# drv8833.net
KiCad netlist of a schematic drawn in EAGLE
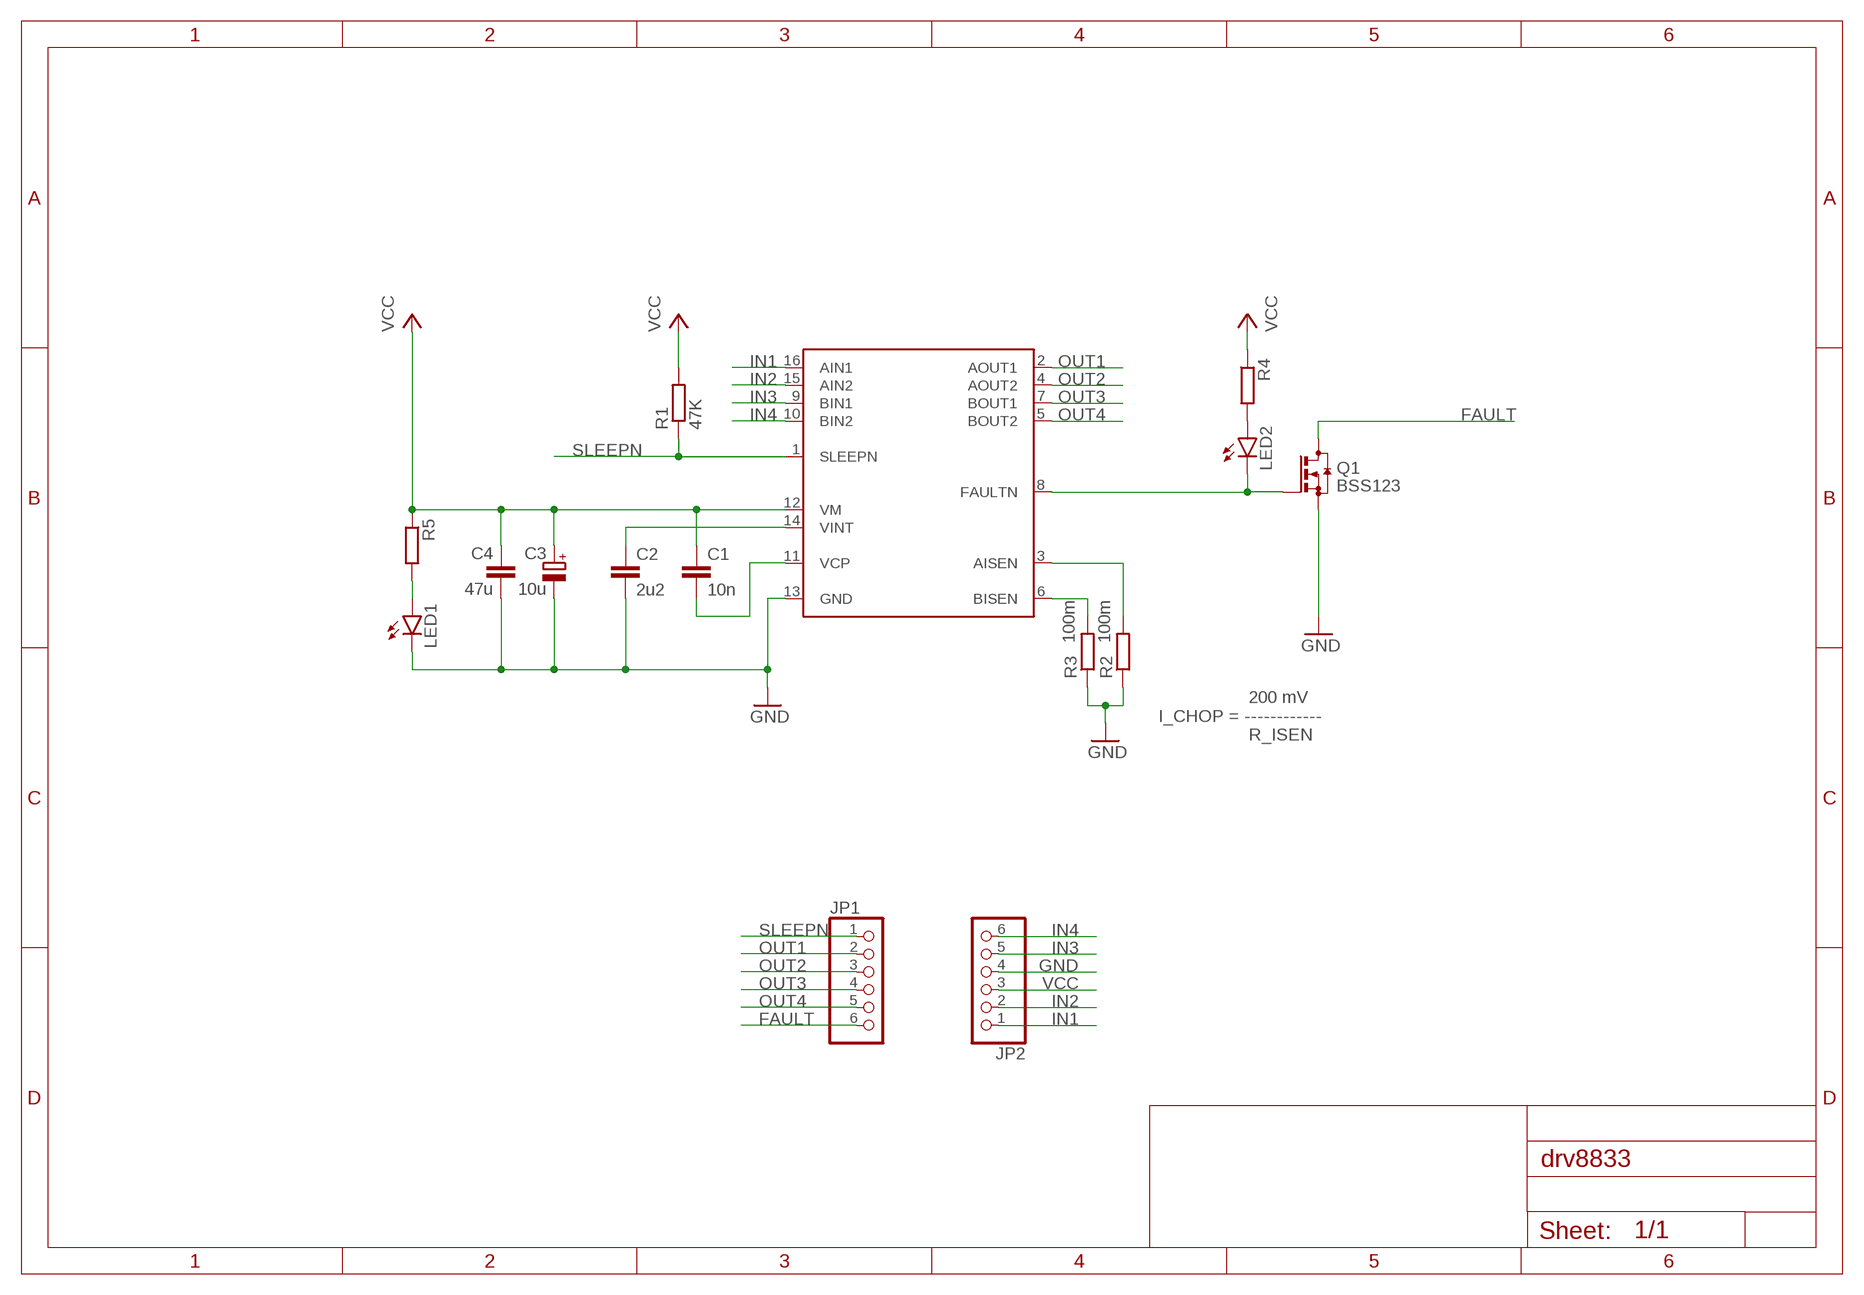
[diagram p0: schematic, sheet 1]

(export (version "E")
  (design (tool "Eeschema 10.0.6"))
  (components
    (comp (ref "C1")
      (value "10n")
      (footprint "eagle-import:C0603")
      (libsource (lib "eagle-import") (part "C0603"))
    )
    (comp (ref "C2")
      (value "2u2")
      (footprint "eagle-import:C0603")
      (libsource (lib "eagle-import") (part "C0603"))
    )
    (comp (ref "C3")
      (value "10u")
      (footprint "eagle-import:A_3216-18W")
      (libsource (lib "eagle-import") (part "CPOL-EUA/3216-18W"))
    )
    (comp (ref "C4")
      (value "47u")
      (footprint "eagle-import:C1210")
      (libsource (lib "eagle-import") (part "C-EUC1210"))
    )
    (comp (ref "JP1")
      (value "PINHD-1X6")
      (footprint "eagle-import:1X06")
      (libsource (lib "eagle-import") (part "PINHD-1X6"))
    )
    (comp (ref "JP2")
      (value "PINHD-1X6")
      (footprint "eagle-import:1X06")
      (libsource (lib "eagle-import") (part "PINHD-1X6"))
    )
    (comp (ref "LED1")
      (value "LEDCHIPLED_0805")
      (footprint "eagle-import:CHIPLED_0805")
      (libsource (lib "eagle-import") (part "LEDCHIPLED_0805"))
    )
    (comp (ref "LED2")
      (value "LEDCHIPLED_0805")
      (footprint "eagle-import:CHIPLED_0805")
      (libsource (lib "eagle-import") (part "LEDCHIPLED_0805"))
    )
    (comp (ref "Q1")
      (value "BSS123")
      (footprint "eagle-import:SOT23")
      (libsource (lib "eagle-import") (part "BSS123"))
    )
    (comp (ref "R1")
      (value "47K")
      (footprint "eagle-import:R0603")
      (libsource (lib "eagle-import") (part "R0603"))
    )
    (comp (ref "R2")
      (value "100m")
      (footprint "eagle-import:R1206")
      (libsource (lib "eagle-import") (part "R-EU_R1206"))
    )
    (comp (ref "R3")
      (value "100m")
      (footprint "eagle-import:R1206")
      (libsource (lib "eagle-import") (part "R-EU_R1206"))
    )
    (comp (ref "R4")
      (value "R0603")
      (footprint "eagle-import:R0603")
      (libsource (lib "eagle-import") (part "R0603"))
    )
    (comp (ref "R5")
      (value "R0603")
      (footprint "eagle-import:R0603")
      (libsource (lib "eagle-import") (part "R0603"))
    )
    (comp (ref "U$1")
      (value "DRV8833")
      (footprint "eagle-import:TSSOP-16")
      (libsource (lib "eagle-import") (part "DRV8833"))
    )
  )
  (nets
    (net (code "1") (name "/FAULT") (class "Default")
      (node (ref "JP1") (pin "6") (pinfunction "6_6") (pintype "passive"))
      (node (ref "Q1") (pin "3") (pinfunction "D_3") (pintype "passive"))
    )
    (net (code "2") (name "/IN1") (class "Default")
      (node (ref "JP2") (pin "1") (pinfunction "1_1") (pintype "passive"))
      (node (ref "U$1") (pin "16") (pinfunction "AIN1_16") (pintype "bidirectional"))
    )
    (net (code "3") (name "/IN2") (class "Default")
      (node (ref "JP2") (pin "2") (pinfunction "2_2") (pintype "passive"))
      (node (ref "U$1") (pin "15") (pinfunction "AIN2_15") (pintype "bidirectional"))
    )
    (net (code "4") (name "/IN3") (class "Default")
      (node (ref "JP2") (pin "5") (pinfunction "5_5") (pintype "passive"))
      (node (ref "U$1") (pin "9") (pinfunction "BIN1_9") (pintype "bidirectional"))
    )
    (net (code "5") (name "/IN4") (class "Default")
      (node (ref "JP2") (pin "6") (pinfunction "6_6") (pintype "passive"))
      (node (ref "U$1") (pin "10") (pinfunction "BIN2_10") (pintype "bidirectional"))
    )
    (net (code "6") (name "/OUT1") (class "Default")
      (node (ref "JP1") (pin "2") (pinfunction "2_2") (pintype "passive"))
      (node (ref "U$1") (pin "2") (pinfunction "AOUT1_2") (pintype "bidirectional"))
    )
    (net (code "7") (name "/OUT2") (class "Default")
      (node (ref "JP1") (pin "3") (pinfunction "3_3") (pintype "passive"))
      (node (ref "U$1") (pin "4") (pinfunction "AOUT2_4") (pintype "bidirectional"))
    )
    (net (code "8") (name "/OUT3") (class "Default")
      (node (ref "JP1") (pin "4") (pinfunction "4_4") (pintype "passive"))
      (node (ref "U$1") (pin "7") (pinfunction "BOUT1_7") (pintype "bidirectional"))
    )
    (net (code "9") (name "/OUT4") (class "Default")
      (node (ref "JP1") (pin "5") (pinfunction "5_5") (pintype "passive"))
      (node (ref "U$1") (pin "5") (pinfunction "BOUT2_5") (pintype "bidirectional"))
    )
    (net (code "10") (name "/SLEEPN") (class "Default")
      (node (ref "JP1") (pin "1") (pinfunction "1_1") (pintype "passive"))
      (node (ref "R1") (pin "1") (pinfunction "1_1") (pintype "passive"))
      (node (ref "U$1") (pin "1") (pinfunction "SLEEPN_1") (pintype "bidirectional"))
    )
    (net (code "11") (name "GND") (class "Default")
      (node (ref "C2") (pin "2") (pinfunction "2_2") (pintype "passive"))
      (node (ref "C3") (pin "-") (pinfunction "-_-") (pintype "passive"))
      (node (ref "C4") (pin "2") (pinfunction "2_2") (pintype "passive"))
      (node (ref "JP2") (pin "4") (pinfunction "4_4") (pintype "passive"))
      (node (ref "LED1") (pin "C") (pinfunction "C_C") (pintype "passive"))
      (node (ref "Q1") (pin "2") (pinfunction "S_2") (pintype "passive"))
      (node (ref "R2") (pin "1") (pinfunction "1_1") (pintype "passive"))
      (node (ref "R3") (pin "1") (pinfunction "1_1") (pintype "passive"))
      (node (ref "U$1") (pin "13") (pinfunction "GND_13") (pintype "bidirectional"))
    )
    (net (code "12") (name "Net-(LED1-PadA)") (class "Default")
      (node (ref "LED1") (pin "A") (pinfunction "A_A") (pintype "passive"))
      (node (ref "R5") (pin "2") (pinfunction "2_2") (pintype "passive"))
    )
    (net (code "13") (name "Net-(LED2-PadA)") (class "Default")
      (node (ref "LED2") (pin "A") (pinfunction "A_A") (pintype "passive"))
      (node (ref "R4") (pin "2") (pinfunction "2_2") (pintype "passive"))
    )
    (net (code "14") (name "Net-(Q1-G)") (class "Default")
      (node (ref "LED2") (pin "C") (pinfunction "C_C") (pintype "passive"))
      (node (ref "Q1") (pin "1") (pinfunction "G_1") (pintype "passive"))
      (node (ref "U$1") (pin "8") (pinfunction "FAULTN_8") (pintype "bidirectional"))
    )
    (net (code "15") (name "Net-(U$1-AISEN)") (class "Default")
      (node (ref "R2") (pin "2") (pinfunction "2_2") (pintype "passive"))
      (node (ref "U$1") (pin "3") (pinfunction "AISEN_3") (pintype "bidirectional"))
    )
    (net (code "16") (name "Net-(U$1-BISEN)") (class "Default")
      (node (ref "R3") (pin "2") (pinfunction "2_2") (pintype "passive"))
      (node (ref "U$1") (pin "6") (pinfunction "BISEN_6") (pintype "bidirectional"))
    )
    (net (code "17") (name "Net-(U$1-VCP)") (class "Default")
      (node (ref "C1") (pin "2") (pinfunction "2_2") (pintype "passive"))
      (node (ref "U$1") (pin "11") (pinfunction "VCP_11") (pintype "bidirectional"))
    )
    (net (code "18") (name "Net-(U$1-VINT)") (class "Default")
      (node (ref "C2") (pin "1") (pinfunction "1_1") (pintype "passive"))
      (node (ref "U$1") (pin "14") (pinfunction "VINT_14") (pintype "bidirectional"))
    )
    (net (code "19") (name "VCC") (class "Default")
      (node (ref "C1") (pin "1") (pinfunction "1_1") (pintype "passive"))
      (node (ref "C3") (pin "+") (pinfunction "+_+") (pintype "passive"))
      (node (ref "C4") (pin "1") (pinfunction "1_1") (pintype "passive"))
      (node (ref "JP2") (pin "3") (pinfunction "3_3") (pintype "passive"))
      (node (ref "R1") (pin "2") (pinfunction "2_2") (pintype "passive"))
      (node (ref "R4") (pin "1") (pinfunction "1_1") (pintype "passive"))
      (node (ref "R5") (pin "1") (pinfunction "1_1") (pintype "passive"))
      (node (ref "U$1") (pin "12") (pinfunction "VM_12") (pintype "bidirectional"))
    )
  )
)
